# Power.net
KiCad netlist of a schematic drawn in Altium Designer
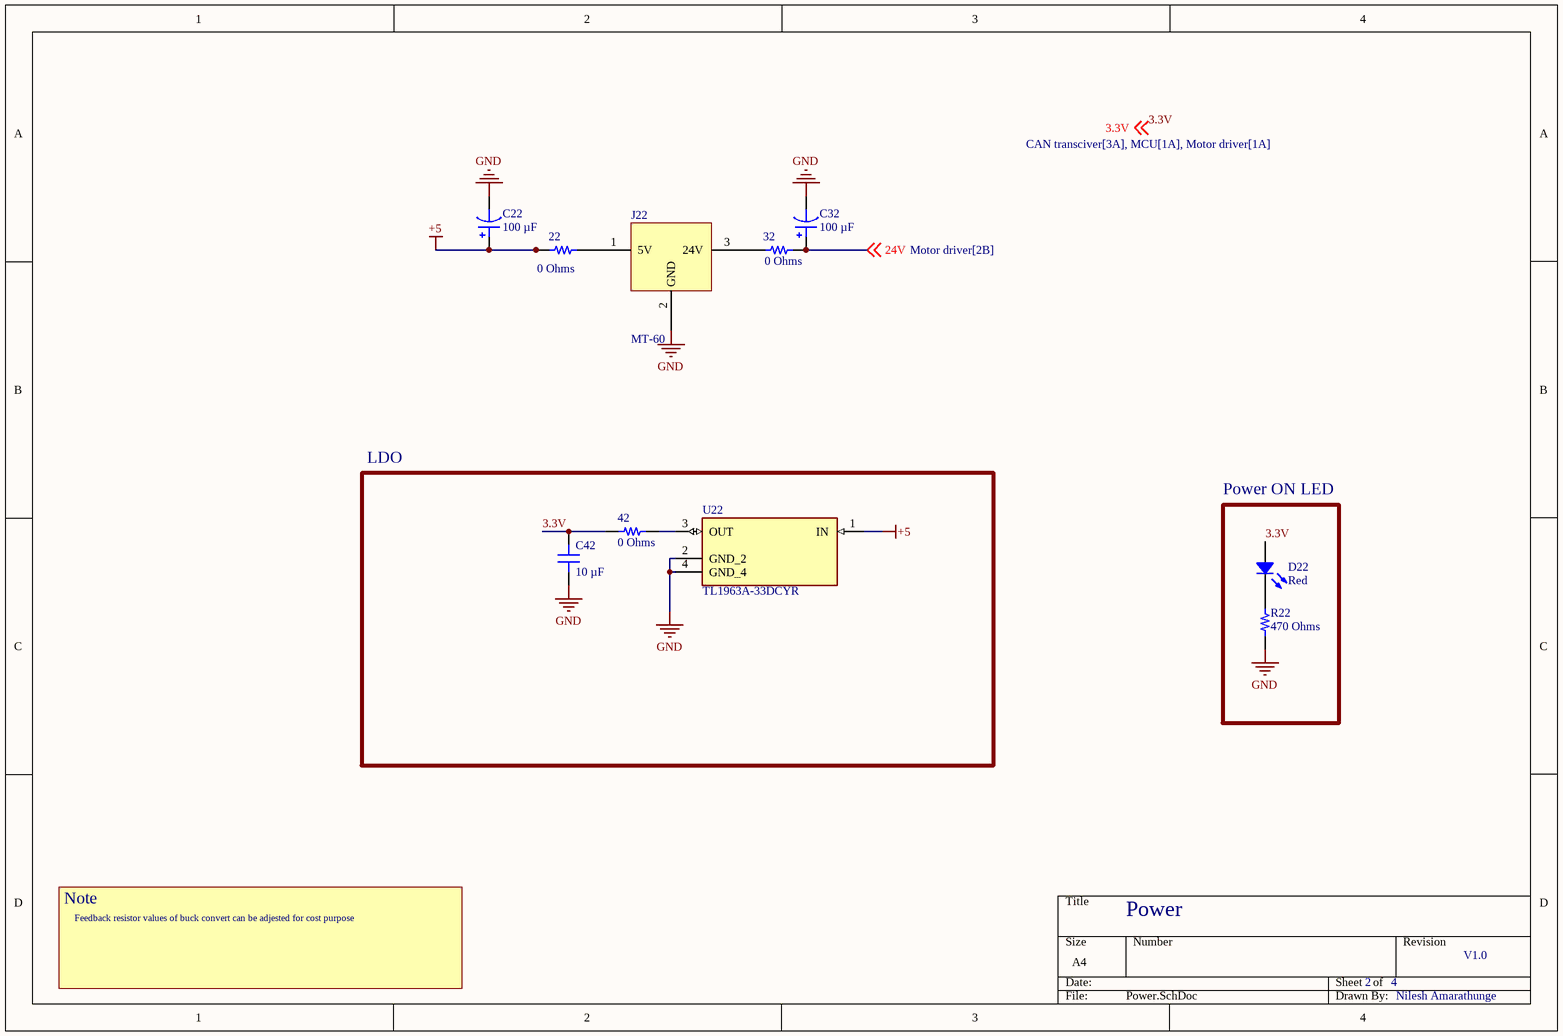
[diagram p0: Power.SchDoc]

(export (version "E")
  (design (tool "Eeschema 10.0.6"))
  (components
    (comp (ref "22")
      (value "0 Ohms")
      (footprint "RES 0805_2012")
      (description "0805 35 AMP JUMPER")
      (fields (field (name "PART NUMBER") "JR0805X35E") (field (name "MANUFACTURER") "Ohmite"))
      (libsource (lib "Celestial Altium Library - altium_library") (part "Resistor"))
    )
    (comp (ref "32")
      (value "0 Ohms")
      (footprint "RES 0805_2012")
      (description "0805 35 AMP JUMPER")
      (fields (field (name "PART NUMBER") "JR0805X35E") (field (name "MANUFACTURER") "Ohmite"))
      (libsource (lib "Celestial Altium Library - altium_library") (part "Resistor"))
    )
    (comp (ref "42")
      (value "0 Ohms")
      (footprint "RES 0805_2012")
      (description "0805 35 AMP JUMPER")
      (fields (field (name "PART NUMBER") "JR0805X35E") (field (name "MANUFACTURER") "Ohmite"))
      (libsource (lib "Celestial Altium Library - altium_library") (part "Resistor"))
    )
    (comp (ref "C22")
      (value "100 µF")
      (footprint "CAP ALSMD 8.3MM H10.5MM")
      (description "CAP ALUM 100UF 20% 50V SMD")
      (fields (field (name "PART NUMBER") "50SKV100M8X10.5") (field (name "MANUFACTURER") "Rubycon"))
      (libsource (lib "Celestial Altium Library - altium_library") (part "Polarised Capacitor"))
    )
    (comp (ref "C32")
      (value "100 µF")
      (footprint "CAP ALSMD 8.3MM H10.5MM")
      (description "CAP ALUM 100UF 20% 50V SMD")
      (fields (field (name "PART NUMBER") "50SKV100M8X10.5") (field (name "MANUFACTURER") "Rubycon"))
      (libsource (lib "Celestial Altium Library - altium_library") (part "Polarised Capacitor"))
    )
    (comp (ref "C42")
      (value "10 µF")
      (footprint "CAP 0805_2012")
      (description "CAP CER 10UF 10V X7R 0805")
      (fields
        (field (name "PART NUMBER") "CL21B106KPQNNNE")
        (field (name "CAPACITANCE") "10 µF")
        (field (name "MANUFACTURER") "Samsung Electro-Mechanics")
      )
      (libsource (lib "Celestial Altium Library - altium_library") (part "Capacitor"))
    )
    (comp (ref "D22")
      (value "Red")
      (footprint "LED 0805_2012 RED")
      (description "LED RED 0805 SMD")
      (fields (field (name "PART NUMBER") "5990110007F") (field (name "MANUFACTURER") "Dialight"))
      (libsource (lib "Celestial Altium Library - altium_library") (part "LED"))
    )
    (comp (ref "J22")
      (value "MT-60")
      (footprint "MT-60")
      (fields (field (name "LCSC PART #") "C99176"))
      (libsource (lib "MT-60") (part "MT-60"))
    )
    (comp (ref "R22")
      (value "470 Ohms")
      (footprint "RES 0805_2012")
      (description "RES SMD 470 OHM 0.1% 1/4W 0805")
      (fields
        (field (name "PART NUMBER") "ERJ-PB6B4700V")
        (field (name "MANUFACTURER") "Panasonic Electronic Components")
      )
      (libsource (lib "Celestial Altium Library - altium_library") (part "Resistor"))
    )
    (comp (ref "U22")
      (value "TL1963A-33DCYR")
      (footprint "VREG_TL1963A-33DCYR")
      (description "1.5-A, 20-V, low-dropout voltage regulator with reverse current & reverse voltage protection")
      (fields (field (name "MF") "Texas Instruments") (field (name "LCSC PART #") "C181262"))
      (libsource (lib "TL1963A-33DCYR") (part "TL1963A-33DCYR"))
    )
  )
  (nets
    (net (code "1") (name "+5") (class "Default")
      (node (ref "22") (pin "1") (pinfunction "1_1") (pintype "passive"))
      (node (ref "C22") (pin "1") (pinfunction "1_1") (pintype "passive"))
      (node (ref "U22") (pin "1") (pinfunction "IN_1") (pintype "input"))
    )
    (net (code "2") (name "3.3V") (class "Default")
      (node (ref "42") (pin "1") (pinfunction "1_1") (pintype "passive"))
      (node (ref "C42") (pin "2") (pinfunction "2_2") (pintype "passive"))
      (node (ref "D22") (pin "1") (pinfunction "1_1") (pintype "passive"))
    )
    (net (code "3") (name "24V") (class "Default")
      (node (ref "32") (pin "2") (pinfunction "2_2") (pintype "passive"))
      (node (ref "C32") (pin "1") (pinfunction "1_1") (pintype "passive"))
    )
    (net (code "4") (name "GND") (class "Default")
      (node (ref "C22") (pin "2") (pinfunction "2_2") (pintype "passive"))
      (node (ref "C32") (pin "2") (pinfunction "2_2") (pintype "passive"))
      (node (ref "C42") (pin "1") (pinfunction "1_1") (pintype "passive"))
      (node (ref "J22") (pin "2") (pinfunction "GND_2") (pintype "passive"))
      (node (ref "R22") (pin "1") (pinfunction "1_1") (pintype "passive"))
      (node (ref "U22") (pin "2") (pinfunction "GND_2_2") (pintype "power_in"))
      (node (ref "U22") (pin "4") (pinfunction "GND_4_4") (pintype "power_in"))
    )
    (net (code "5") (name "Net-(D22-Pad2)") (class "Default")
      (node (ref "D22") (pin "2") (pinfunction "2_2") (pintype "passive"))
      (node (ref "R22") (pin "2") (pinfunction "2_2") (pintype "passive"))
    )
    (net (code "6") (name "Net-(J22-5V)") (class "Default")
      (node (ref "22") (pin "2") (pinfunction "2_2") (pintype "passive"))
      (node (ref "J22") (pin "1") (pinfunction "5V_1") (pintype "passive"))
    )
    (net (code "7") (name "Net-(J22-24V)") (class "Default")
      (node (ref "32") (pin "1") (pinfunction "1_1") (pintype "passive"))
      (node (ref "J22") (pin "3") (pinfunction "24V_3") (pintype "passive"))
    )
    (net (code "8") (name "Net-(U22-OUT)") (class "Default")
      (node (ref "42") (pin "2") (pinfunction "2_2") (pintype "passive"))
      (node (ref "U22") (pin "3") (pinfunction "OUT_3") (pintype "bidirectional"))
    )
  )
)
